# zdroj5V.net
KiCad netlist of a schematic drawn in EAGLE
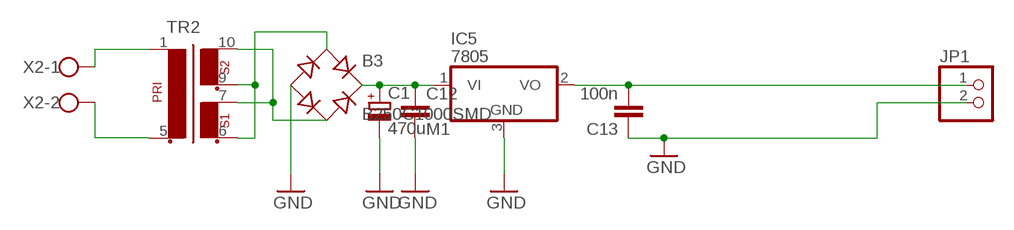
[diagram p0: schematic, sheet 1]

(export (version "E")
  (design (tool "Eeschema 10.0.6"))
  (components
    (comp (ref "B3")
      (value "B250C1000SMD")
      (footprint "eagle-import:B40S")
      (libsource (lib "eagle-import") (part "RECTIFIER-B40S"))
    )
    (comp (ref "C1")
      (value "470u")
      (footprint "eagle-import:E5-10,5")
      (libsource (lib "eagle-import") (part "CPOL-EUE5-10.5"))
    )
    (comp (ref "C12")
      (value "M1")
      (footprint "eagle-import:C1206")
      (libsource (lib "eagle-import") (part "C-EUC1206"))
    )
    (comp (ref "C13")
      (value "100n")
      (footprint "eagle-import:C1206")
      (libsource (lib "eagle-import") (part "C-EUC1206"))
    )
    (comp (ref "IC5")
      (value "7805")
      (footprint "eagle-import:TO252")
      (libsource (lib "eagle-import") (part "78DT06"))
    )
    (comp (ref "JP1")
      (value "PINHD-1X2")
      (footprint "eagle-import:1X02")
      (libsource (lib "eagle-import") (part "PINHD-1X2"))
    )
    (comp (ref "TR2")
      (value "EI30-2")
      (footprint "eagle-import:EI30-2")
      (libsource (lib "eagle-import") (part "EI30-2"))
    )
    (comp (ref "X2")
      (value "W237-102")
      (footprint "eagle-import:W237-102")
      (fields (field (name "MPN") "237-102"))
      (libsource (lib "eagle-import") (part "W237-102"))
    )
  )
  (nets
    (net (code "1") (name "GND") (class "Default")
      (node (ref "B3") (pin "-") (pinfunction "-_-") (pintype "passive"))
      (node (ref "C1") (pin "-") (pinfunction "-_-") (pintype "passive"))
      (node (ref "C12") (pin "2") (pinfunction "2_2") (pintype "passive"))
      (node (ref "C13") (pin "1") (pinfunction "1_1") (pintype "passive"))
      (node (ref "IC5") (pin "3") (pinfunction "GND_3") (pintype "passive"))
      (node (ref "JP1") (pin "2") (pinfunction "2_2") (pintype "passive"))
    )
    (net (code "2") (name "Net-(IC5-VI)") (class "Default")
      (node (ref "B3") (pin "+") (pinfunction "+_+") (pintype "passive"))
      (node (ref "C1") (pin "+") (pinfunction "+_+") (pintype "passive"))
      (node (ref "C12") (pin "1") (pinfunction "1_1") (pintype "passive"))
      (node (ref "IC5") (pin "1") (pinfunction "VI_1") (pintype "input"))
    )
    (net (code "3") (name "Net-(IC5-VO)") (class "Default")
      (node (ref "C13") (pin "2") (pinfunction "2_2") (pintype "passive"))
      (node (ref "IC5") (pin "2") (pinfunction "VO_2") (pintype "passive"))
      (node (ref "JP1") (pin "1") (pinfunction "1_1") (pintype "passive"))
    )
    (net (code "4") (name "Net-(TR2-2)") (class "Default")
      (node (ref "TR2") (pin "5") (pinfunction "2_5") (pintype "passive"))
      (node (ref "X2") (pin "2") (pinfunction "KL_2") (pintype "passive"))
    )
    (net (code "5") (name "Net-(TR2-3)") (class "Default")
      (node (ref "B3") (pin "AC1") (pinfunction "AC1_AC1") (pintype "passive"))
      (node (ref "TR2") (pin "6") (pinfunction "3_6") (pintype "passive"))
      (node (ref "TR2") (pin "9") (pinfunction "5_9") (pintype "passive"))
    )
    (net (code "6") (name "Net-(TR2-4)") (class "Default")
      (node (ref "B3") (pin "AC2") (pinfunction "AC2_AC2") (pintype "passive"))
      (node (ref "TR2") (pin "10") (pinfunction "6_10") (pintype "passive"))
      (node (ref "TR2") (pin "7") (pinfunction "4_7") (pintype "passive"))
    )
    (net (code "7") (name "Net-(X2A-KL)") (class "Default")
      (node (ref "TR2") (pin "1") (pinfunction "1_1") (pintype "passive"))
      (node (ref "X2") (pin "1") (pinfunction "KL_1") (pintype "passive"))
    )
  )
)
